# sdram_xsd.net
KiCad netlist of a schematic drawn in Altium Designer
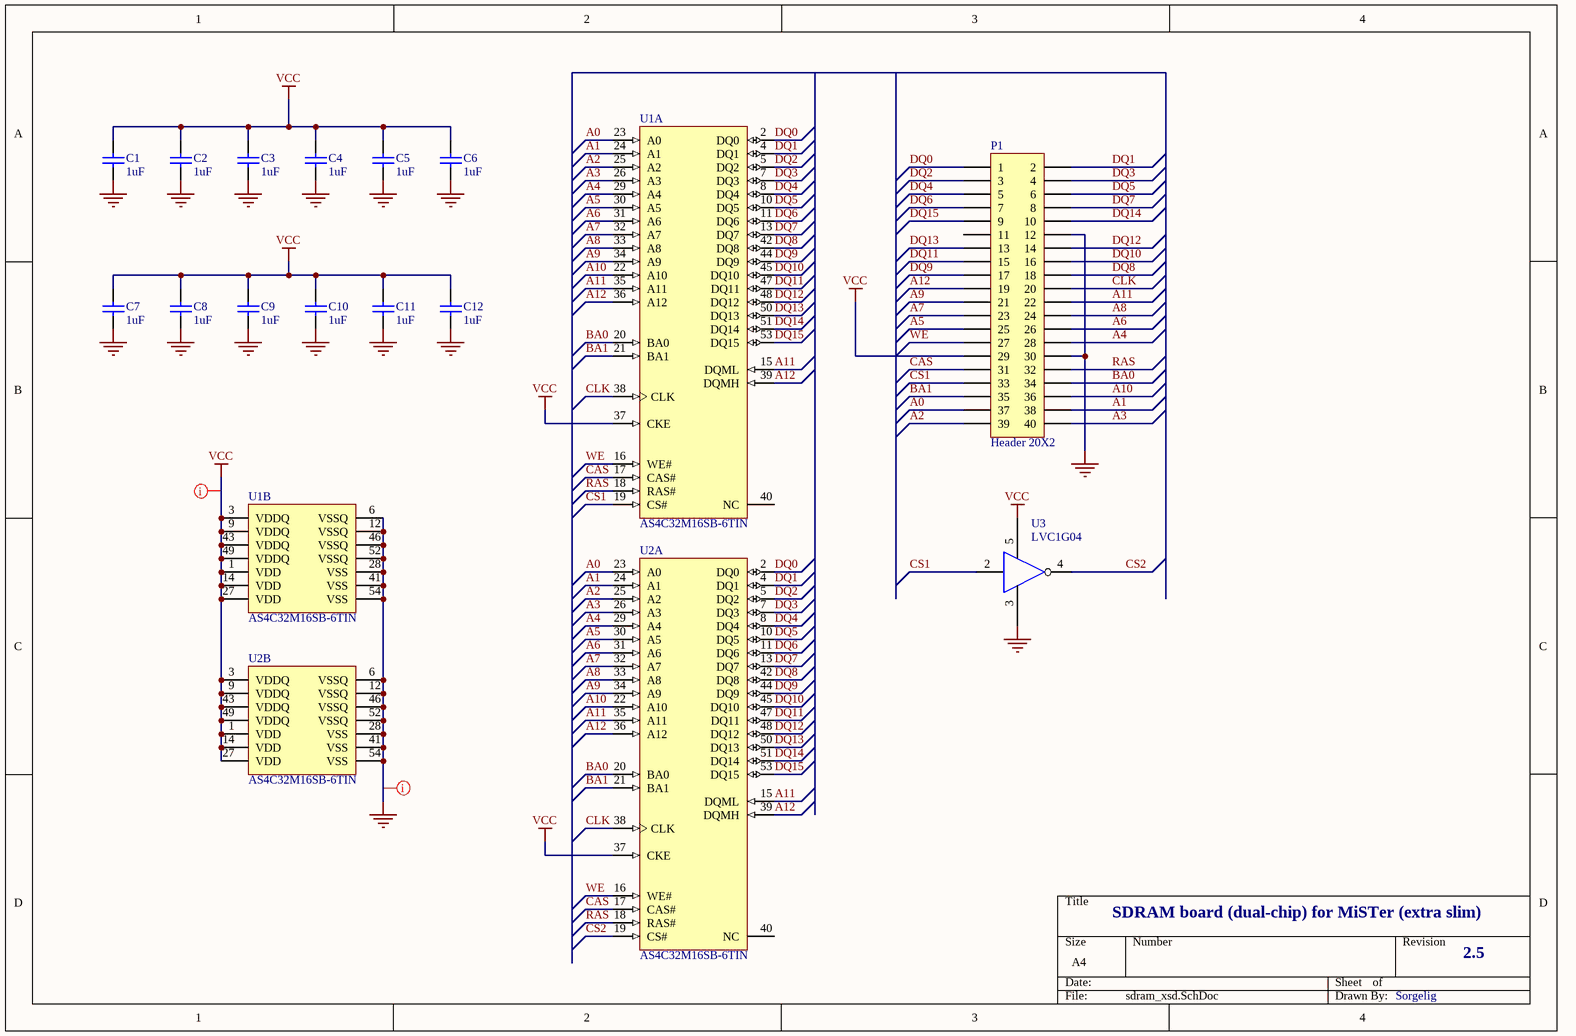
[diagram p0: sdram_xsd.SchDoc]

(export (version "E")
  (design (tool "Eeschema 10.0.6"))
  (components
    (comp (ref "C1")
      (value "1uF")
      (footprint "C0805")
      (description "Ceramic Chip Capacitor - Standard")
      (fields (field (name "Comment") "C0805") (field (name "PUBLISHER") "Altium Limited"))
      (libsource (lib "lib") (part "C0805"))
    )
    (comp (ref "C2")
      (value "1uF")
      (footprint "C0805")
      (description "Ceramic Chip Capacitor - Standard")
      (fields (field (name "Comment") "C0805") (field (name "PUBLISHER") "Altium Limited"))
      (libsource (lib "lib") (part "C0805"))
    )
    (comp (ref "C3")
      (value "1uF")
      (footprint "C0805")
      (description "Ceramic Chip Capacitor - Standard")
      (fields (field (name "Comment") "+") (field (name "PUBLISHER") "Altium Limited"))
      (libsource (lib "lib") (part "C0805"))
    )
    (comp (ref "C4")
      (value "1uF")
      (footprint "C0805")
      (description "Ceramic Chip Capacitor - Standard")
      (fields (field (name "Comment") "C0805") (field (name "PUBLISHER") "Altium Limited"))
      (libsource (lib "lib") (part "C0805"))
    )
    (comp (ref "C5")
      (value "1uF")
      (footprint "C0805")
      (description "Ceramic Chip Capacitor - Standard")
      (fields (field (name "Comment") "+") (field (name "PUBLISHER") "Altium Limited"))
      (libsource (lib "lib") (part "C0805"))
    )
    (comp (ref "C6")
      (value "1uF")
      (footprint "C0805")
      (description "Ceramic Chip Capacitor - Standard")
      (fields (field (name "Comment") "+") (field (name "PUBLISHER") "Altium Limited"))
      (libsource (lib "lib") (part "C0805"))
    )
    (comp (ref "C7")
      (value "1uF")
      (footprint "C0805")
      (description "Ceramic Chip Capacitor - Standard")
      (fields (field (name "Comment") "C0805") (field (name "PUBLISHER") "Altium Limited"))
      (libsource (lib "lib") (part "C0805"))
    )
    (comp (ref "C8")
      (value "1uF")
      (footprint "C0805")
      (description "Ceramic Chip Capacitor - Standard")
      (fields (field (name "Comment") "C0805") (field (name "PUBLISHER") "Altium Limited"))
      (libsource (lib "lib") (part "C0805"))
    )
    (comp (ref "C9")
      (value "1uF")
      (footprint "C0805")
      (description "Ceramic Chip Capacitor - Standard")
      (fields (field (name "Comment") "+") (field (name "PUBLISHER") "Altium Limited"))
      (libsource (lib "lib") (part "C0805"))
    )
    (comp (ref "C10")
      (value "1uF")
      (footprint "C0805")
      (description "Ceramic Chip Capacitor - Standard")
      (fields (field (name "Comment") "C0805") (field (name "PUBLISHER") "Altium Limited"))
      (libsource (lib "lib") (part "C0805"))
    )
    (comp (ref "C11")
      (value "1uF")
      (footprint "C0805")
      (description "Ceramic Chip Capacitor - Standard")
      (fields (field (name "Comment") "C0805") (field (name "PUBLISHER") "Altium Limited"))
      (libsource (lib "lib") (part "C0805"))
    )
    (comp (ref "C12")
      (value "1uF")
      (footprint "C0805")
      (description "Ceramic Chip Capacitor - Standard")
      (fields (field (name "Comment") "+") (field (name "PUBLISHER") "Altium Limited"))
      (libsource (lib "lib") (part "C0805"))
    )
    (comp (ref "P1")
      (value "Header 20X2")
      (footprint "HDR20x2_90")
      (description "Header, 20-Pin, Dual row")
      (fields (field (name "PUBLISHER") "Altium Limited"))
      (libsource (lib "Miscellaneous Connectors") (part "Header 20X2"))
    )
    (comp (ref "U1")
      (value "AS4C32M16SB-6TIN")
      (footprint "TSOP54")
      (description "256Mb SDR SDRAM, 16Mb x 16, 6ns, 3.3V, 54-Pin TSOP")
      (fields (field (name "VOLTAGE") "3.3V ") (field (name "MANUFACTURER") "Micron"))
      (libsource (lib "lib") (part "AS4C16M16SA-6TCN"))
    )
    (comp (ref "U2")
      (value "AS4C32M16SB-6TIN")
      (footprint "TSOP54")
      (description "256Mb SDR SDRAM, 16Mb x 16, 6ns, 3.3V, 54-Pin TSOP")
      (fields (field (name "VOLTAGE") "3.3V ") (field (name "MANUFACTURER") "Micron"))
      (libsource (lib "lib") (part "AS4C16M16SA-6TCN"))
    )
    (comp (ref "U3")
      (value "LVC1G04")
      (footprint "SOT23/70-5")
      (description "INVERTER")
      (libsource (lib "lib") (part "LVC1G04"))
    )
  )
  (nets
    (net (code "1") (name "/A0") (class "Default")
      (node (ref "P1") (pin "37") (pinfunction "37_37") (pintype "passive"))
      (node (ref "U1") (pin "23") (pinfunction "A0_23") (pintype "input"))
      (node (ref "U2") (pin "23") (pinfunction "A0_23") (pintype "input"))
    )
    (net (code "2") (name "/A1") (class "Default")
      (node (ref "P1") (pin "38") (pinfunction "38_38") (pintype "passive"))
      (node (ref "U1") (pin "24") (pinfunction "A1_24") (pintype "input"))
      (node (ref "U2") (pin "24") (pinfunction "A1_24") (pintype "input"))
    )
    (net (code "3") (name "/A2") (class "Default")
      (node (ref "P1") (pin "39") (pinfunction "39_39") (pintype "passive"))
      (node (ref "U1") (pin "25") (pinfunction "A2_25") (pintype "input"))
      (node (ref "U2") (pin "25") (pinfunction "A2_25") (pintype "input"))
    )
    (net (code "4") (name "/A3") (class "Default")
      (node (ref "P1") (pin "40") (pinfunction "40_40") (pintype "passive"))
      (node (ref "U1") (pin "26") (pinfunction "A3_26") (pintype "input"))
      (node (ref "U2") (pin "26") (pinfunction "A3_26") (pintype "input"))
    )
    (net (code "5") (name "/A4") (class "Default")
      (node (ref "P1") (pin "28") (pinfunction "28_28") (pintype "passive"))
      (node (ref "U1") (pin "29") (pinfunction "A4_29") (pintype "input"))
      (node (ref "U2") (pin "29") (pinfunction "A4_29") (pintype "input"))
    )
    (net (code "6") (name "/A5") (class "Default")
      (node (ref "P1") (pin "25") (pinfunction "25_25") (pintype "passive"))
      (node (ref "U1") (pin "30") (pinfunction "A5_30") (pintype "input"))
      (node (ref "U2") (pin "30") (pinfunction "A5_30") (pintype "input"))
    )
    (net (code "7") (name "/A6") (class "Default")
      (node (ref "P1") (pin "26") (pinfunction "26_26") (pintype "passive"))
      (node (ref "U1") (pin "31") (pinfunction "A6_31") (pintype "input"))
      (node (ref "U2") (pin "31") (pinfunction "A6_31") (pintype "input"))
    )
    (net (code "8") (name "/A7") (class "Default")
      (node (ref "P1") (pin "23") (pinfunction "23_23") (pintype "passive"))
      (node (ref "U1") (pin "32") (pinfunction "A7_32") (pintype "input"))
      (node (ref "U2") (pin "32") (pinfunction "A7_32") (pintype "input"))
    )
    (net (code "9") (name "/A8") (class "Default")
      (node (ref "P1") (pin "24") (pinfunction "24_24") (pintype "passive"))
      (node (ref "U1") (pin "33") (pinfunction "A8_33") (pintype "input"))
      (node (ref "U2") (pin "33") (pinfunction "A8_33") (pintype "input"))
    )
    (net (code "10") (name "/A9") (class "Default")
      (node (ref "P1") (pin "21") (pinfunction "21_21") (pintype "passive"))
      (node (ref "U1") (pin "34") (pinfunction "A9_34") (pintype "input"))
      (node (ref "U2") (pin "34") (pinfunction "A9_34") (pintype "input"))
    )
    (net (code "11") (name "/A10") (class "Default")
      (node (ref "P1") (pin "36") (pinfunction "36_36") (pintype "passive"))
      (node (ref "U1") (pin "22") (pinfunction "A10_22") (pintype "input"))
      (node (ref "U2") (pin "22") (pinfunction "A10_22") (pintype "input"))
    )
    (net (code "12") (name "/A11") (class "Default")
      (node (ref "P1") (pin "22") (pinfunction "22_22") (pintype "passive"))
      (node (ref "U1") (pin "15") (pinfunction "DQML_15") (pintype "input"))
      (node (ref "U1") (pin "35") (pinfunction "A11_35") (pintype "input"))
      (node (ref "U2") (pin "15") (pinfunction "DQML_15") (pintype "input"))
      (node (ref "U2") (pin "35") (pinfunction "A11_35") (pintype "input"))
    )
    (net (code "13") (name "/A12") (class "Default")
      (node (ref "P1") (pin "19") (pinfunction "19_19") (pintype "passive"))
      (node (ref "U1") (pin "36") (pinfunction "A12_36") (pintype "input"))
      (node (ref "U1") (pin "39") (pinfunction "DQMH_39") (pintype "input"))
      (node (ref "U2") (pin "36") (pinfunction "A12_36") (pintype "input"))
      (node (ref "U2") (pin "39") (pinfunction "DQMH_39") (pintype "input"))
    )
    (net (code "14") (name "/BA0") (class "Default")
      (node (ref "P1") (pin "34") (pinfunction "34_34") (pintype "passive"))
      (node (ref "U1") (pin "20") (pinfunction "BA0_20") (pintype "input"))
      (node (ref "U2") (pin "20") (pinfunction "BA0_20") (pintype "input"))
    )
    (net (code "15") (name "/BA1") (class "Default")
      (node (ref "P1") (pin "35") (pinfunction "35_35") (pintype "passive"))
      (node (ref "U1") (pin "21") (pinfunction "BA1_21") (pintype "input"))
      (node (ref "U2") (pin "21") (pinfunction "BA1_21") (pintype "input"))
    )
    (net (code "16") (name "/CAS") (class "Default")
      (node (ref "P1") (pin "31") (pinfunction "31_31") (pintype "passive"))
      (node (ref "U1") (pin "17") (pinfunction "CAS#_17") (pintype "input"))
      (node (ref "U2") (pin "17") (pinfunction "CAS#_17") (pintype "input"))
    )
    (net (code "17") (name "/CLK") (class "Default")
      (node (ref "P1") (pin "20") (pinfunction "20_20") (pintype "passive"))
      (node (ref "U1") (pin "38") (pinfunction "CLK_38") (pintype "input"))
      (node (ref "U2") (pin "38") (pinfunction "CLK_38") (pintype "input"))
    )
    (net (code "18") (name "/CS1") (class "Default")
      (node (ref "P1") (pin "33") (pinfunction "33_33") (pintype "passive"))
      (node (ref "U1") (pin "19") (pinfunction "CS#_19") (pintype "input"))
      (node (ref "U3") (pin "2") (pinfunction "A_2") (pintype "passive"))
    )
    (net (code "19") (name "/CS2") (class "Default")
      (node (ref "U2") (pin "19") (pinfunction "CS#_19") (pintype "input"))
      (node (ref "U3") (pin "4") (pinfunction "Y_4") (pintype "passive"))
    )
    (net (code "20") (name "/DQ0") (class "Default")
      (node (ref "P1") (pin "1") (pinfunction "1_1") (pintype "passive"))
      (node (ref "U1") (pin "2") (pinfunction "DQ0_2") (pintype "bidirectional"))
      (node (ref "U2") (pin "2") (pinfunction "DQ0_2") (pintype "bidirectional"))
    )
    (net (code "21") (name "/DQ1") (class "Default")
      (node (ref "P1") (pin "2") (pinfunction "2_2") (pintype "passive"))
      (node (ref "U1") (pin "4") (pinfunction "DQ1_4") (pintype "bidirectional"))
      (node (ref "U2") (pin "4") (pinfunction "DQ1_4") (pintype "bidirectional"))
    )
    (net (code "22") (name "/DQ2") (class "Default")
      (node (ref "P1") (pin "3") (pinfunction "3_3") (pintype "passive"))
      (node (ref "U1") (pin "5") (pinfunction "DQ2_5") (pintype "bidirectional"))
      (node (ref "U2") (pin "5") (pinfunction "DQ2_5") (pintype "bidirectional"))
    )
    (net (code "23") (name "/DQ3") (class "Default")
      (node (ref "P1") (pin "4") (pinfunction "4_4") (pintype "passive"))
      (node (ref "U1") (pin "7") (pinfunction "DQ3_7") (pintype "bidirectional"))
      (node (ref "U2") (pin "7") (pinfunction "DQ3_7") (pintype "bidirectional"))
    )
    (net (code "24") (name "/DQ4") (class "Default")
      (node (ref "P1") (pin "5") (pinfunction "5_5") (pintype "passive"))
      (node (ref "U1") (pin "8") (pinfunction "DQ4_8") (pintype "bidirectional"))
      (node (ref "U2") (pin "8") (pinfunction "DQ4_8") (pintype "bidirectional"))
    )
    (net (code "25") (name "/DQ5") (class "Default")
      (node (ref "P1") (pin "6") (pinfunction "6_6") (pintype "passive"))
      (node (ref "U1") (pin "10") (pinfunction "DQ5_10") (pintype "bidirectional"))
      (node (ref "U2") (pin "10") (pinfunction "DQ5_10") (pintype "bidirectional"))
    )
    (net (code "26") (name "/DQ6") (class "Default")
      (node (ref "P1") (pin "7") (pinfunction "7_7") (pintype "passive"))
      (node (ref "U1") (pin "11") (pinfunction "DQ6_11") (pintype "bidirectional"))
      (node (ref "U2") (pin "11") (pinfunction "DQ6_11") (pintype "bidirectional"))
    )
    (net (code "27") (name "/DQ7") (class "Default")
      (node (ref "P1") (pin "8") (pinfunction "8_8") (pintype "passive"))
      (node (ref "U1") (pin "13") (pinfunction "DQ7_13") (pintype "bidirectional"))
      (node (ref "U2") (pin "13") (pinfunction "DQ7_13") (pintype "bidirectional"))
    )
    (net (code "28") (name "/DQ8") (class "Default")
      (node (ref "P1") (pin "18") (pinfunction "18_18") (pintype "passive"))
      (node (ref "U1") (pin "42") (pinfunction "DQ8_42") (pintype "bidirectional"))
      (node (ref "U2") (pin "42") (pinfunction "DQ8_42") (pintype "bidirectional"))
    )
    (net (code "29") (name "/DQ9") (class "Default")
      (node (ref "P1") (pin "17") (pinfunction "17_17") (pintype "passive"))
      (node (ref "U1") (pin "44") (pinfunction "DQ9_44") (pintype "bidirectional"))
      (node (ref "U2") (pin "44") (pinfunction "DQ9_44") (pintype "bidirectional"))
    )
    (net (code "30") (name "/DQ10") (class "Default")
      (node (ref "P1") (pin "16") (pinfunction "16_16") (pintype "passive"))
      (node (ref "U1") (pin "45") (pinfunction "DQ10_45") (pintype "bidirectional"))
      (node (ref "U2") (pin "45") (pinfunction "DQ10_45") (pintype "bidirectional"))
    )
    (net (code "31") (name "/DQ11") (class "Default")
      (node (ref "P1") (pin "15") (pinfunction "15_15") (pintype "passive"))
      (node (ref "U1") (pin "47") (pinfunction "DQ11_47") (pintype "bidirectional"))
      (node (ref "U2") (pin "47") (pinfunction "DQ11_47") (pintype "bidirectional"))
    )
    (net (code "32") (name "/DQ12") (class "Default")
      (node (ref "P1") (pin "14") (pinfunction "14_14") (pintype "passive"))
      (node (ref "U1") (pin "48") (pinfunction "DQ12_48") (pintype "bidirectional"))
      (node (ref "U2") (pin "48") (pinfunction "DQ12_48") (pintype "bidirectional"))
    )
    (net (code "33") (name "/DQ13") (class "Default")
      (node (ref "P1") (pin "13") (pinfunction "13_13") (pintype "passive"))
      (node (ref "U1") (pin "50") (pinfunction "DQ13_50") (pintype "bidirectional"))
      (node (ref "U2") (pin "50") (pinfunction "DQ13_50") (pintype "bidirectional"))
    )
    (net (code "34") (name "/DQ14") (class "Default")
      (node (ref "P1") (pin "10") (pinfunction "10_10") (pintype "passive"))
      (node (ref "U1") (pin "51") (pinfunction "DQ14_51") (pintype "bidirectional"))
      (node (ref "U2") (pin "51") (pinfunction "DQ14_51") (pintype "bidirectional"))
    )
    (net (code "35") (name "/DQ15") (class "Default")
      (node (ref "P1") (pin "9") (pinfunction "9_9") (pintype "passive"))
      (node (ref "U1") (pin "53") (pinfunction "DQ15_53") (pintype "bidirectional"))
      (node (ref "U2") (pin "53") (pinfunction "DQ15_53") (pintype "bidirectional"))
    )
    (net (code "36") (name "/RAS") (class "Default")
      (node (ref "P1") (pin "32") (pinfunction "32_32") (pintype "passive"))
      (node (ref "U1") (pin "18") (pinfunction "RAS#_18") (pintype "input"))
      (node (ref "U2") (pin "18") (pinfunction "RAS#_18") (pintype "input"))
    )
    (net (code "37") (name "/WE") (class "Default")
      (node (ref "P1") (pin "27") (pinfunction "27_27") (pintype "passive"))
      (node (ref "U1") (pin "16") (pinfunction "WE#_16") (pintype "input"))
      (node (ref "U2") (pin "16") (pinfunction "WE#_16") (pintype "input"))
    )
    (net (code "38") (name "GND") (class "Default")
      (node (ref "C1") (pin "1") (pinfunction "1_1") (pintype "passive"))
      (node (ref "C10") (pin "1") (pinfunction "1_1") (pintype "passive"))
      (node (ref "C11") (pin "1") (pinfunction "1_1") (pintype "passive"))
      (node (ref "C12") (pin "1") (pinfunction "1_1") (pintype "passive"))
      (node (ref "C2") (pin "1") (pinfunction "1_1") (pintype "passive"))
      (node (ref "C3") (pin "1") (pinfunction "1_1") (pintype "passive"))
      (node (ref "C4") (pin "1") (pinfunction "1_1") (pintype "passive"))
      (node (ref "C5") (pin "1") (pinfunction "1_1") (pintype "passive"))
      (node (ref "C6") (pin "1") (pinfunction "1_1") (pintype "passive"))
      (node (ref "C7") (pin "1") (pinfunction "1_1") (pintype "passive"))
      (node (ref "C8") (pin "1") (pinfunction "1_1") (pintype "passive"))
      (node (ref "C9") (pin "1") (pinfunction "1_1") (pintype "passive"))
      (node (ref "P1") (pin "12") (pinfunction "12_12") (pintype "power_in"))
      (node (ref "P1") (pin "30") (pinfunction "30_30") (pintype "power_in"))
      (node (ref "U1") (pin "12") (pinfunction "VSSQ_12") (pintype "power_in"))
      (node (ref "U1") (pin "28") (pinfunction "VSS_28") (pintype "power_in"))
      (node (ref "U1") (pin "41") (pinfunction "VSS_41") (pintype "power_in"))
      (node (ref "U1") (pin "46") (pinfunction "VSSQ_46") (pintype "power_in"))
      (node (ref "U1") (pin "52") (pinfunction "VSSQ_52") (pintype "power_in"))
      (node (ref "U1") (pin "54") (pinfunction "VSS_54") (pintype "power_in"))
      (node (ref "U1") (pin "6") (pinfunction "VSSQ_6") (pintype "power_in"))
      (node (ref "U2") (pin "12") (pinfunction "VSSQ_12") (pintype "power_in"))
      (node (ref "U2") (pin "28") (pinfunction "VSS_28") (pintype "power_in"))
      (node (ref "U2") (pin "41") (pinfunction "VSS_41") (pintype "power_in"))
      (node (ref "U2") (pin "46") (pinfunction "VSSQ_46") (pintype "power_in"))
      (node (ref "U2") (pin "52") (pinfunction "VSSQ_52") (pintype "power_in"))
      (node (ref "U2") (pin "54") (pinfunction "VSS_54") (pintype "power_in"))
      (node (ref "U2") (pin "6") (pinfunction "VSSQ_6") (pintype "power_in"))
      (node (ref "U3") (pin "3") (pinfunction "GND_3") (pintype "passive"))
    )
    (net (code "39") (name "VCC") (class "Default")
      (node (ref "C1") (pin "2") (pinfunction "2_2") (pintype "passive"))
      (node (ref "C10") (pin "2") (pinfunction "2_2") (pintype "passive"))
      (node (ref "C11") (pin "2") (pinfunction "2_2") (pintype "passive"))
      (node (ref "C12") (pin "2") (pinfunction "2_2") (pintype "passive"))
      (node (ref "C2") (pin "2") (pinfunction "2_2") (pintype "passive"))
      (node (ref "C3") (pin "2") (pinfunction "2_2") (pintype "passive"))
      (node (ref "C4") (pin "2") (pinfunction "2_2") (pintype "passive"))
      (node (ref "C5") (pin "2") (pinfunction "2_2") (pintype "passive"))
      (node (ref "C6") (pin "2") (pinfunction "2_2") (pintype "passive"))
      (node (ref "C7") (pin "2") (pinfunction "2_2") (pintype "passive"))
      (node (ref "C8") (pin "2") (pinfunction "2_2") (pintype "passive"))
      (node (ref "C9") (pin "2") (pinfunction "2_2") (pintype "passive"))
      (node (ref "P1") (pin "29") (pinfunction "29_29") (pintype "power_in"))
      (node (ref "U1") (pin "1") (pinfunction "VDD_1") (pintype "power_in"))
      (node (ref "U1") (pin "14") (pinfunction "VDD_14") (pintype "power_in"))
      (node (ref "U1") (pin "27") (pinfunction "VDD_27") (pintype "power_in"))
      (node (ref "U1") (pin "3") (pinfunction "VDDQ_3") (pintype "power_in"))
      (node (ref "U1") (pin "37") (pinfunction "CKE_37") (pintype "input"))
      (node (ref "U1") (pin "43") (pinfunction "VDDQ_43") (pintype "power_in"))
      (node (ref "U1") (pin "49") (pinfunction "VDDQ_49") (pintype "power_in"))
      (node (ref "U1") (pin "9") (pinfunction "VDDQ_9") (pintype "power_in"))
      (node (ref "U2") (pin "1") (pinfunction "VDD_1") (pintype "power_in"))
      (node (ref "U2") (pin "14") (pinfunction "VDD_14") (pintype "power_in"))
      (node (ref "U2") (pin "27") (pinfunction "VDD_27") (pintype "power_in"))
      (node (ref "U2") (pin "3") (pinfunction "VDDQ_3") (pintype "power_in"))
      (node (ref "U2") (pin "37") (pinfunction "CKE_37") (pintype "input"))
      (node (ref "U2") (pin "43") (pinfunction "VDDQ_43") (pintype "power_in"))
      (node (ref "U2") (pin "49") (pinfunction "VDDQ_49") (pintype "power_in"))
      (node (ref "U2") (pin "9") (pinfunction "VDDQ_9") (pintype "power_in"))
      (node (ref "U3") (pin "5") (pinfunction "VCC_5") (pintype "passive"))
    )
    (net (code "40") (name "unconnected-(P1-Pad11)") (class "Default")
      (node (ref "P1") (pin "11") (pinfunction "11_11") (pintype "power_in"))
    )
    (net (code "41") (name "unconnected-(U1A-NC-Pad40)") (class "Default")
      (node (ref "U1") (pin "40") (pinfunction "NC_40") (pintype "passive"))
    )
    (net (code "42") (name "unconnected-(U2A-NC-Pad40)") (class "Default")
      (node (ref "U2") (pin "40") (pinfunction "NC_40") (pintype "passive"))
    )
  )
)
